# segment_driver_large.net
KiCad netlist of a schematic drawn in Altium Designer
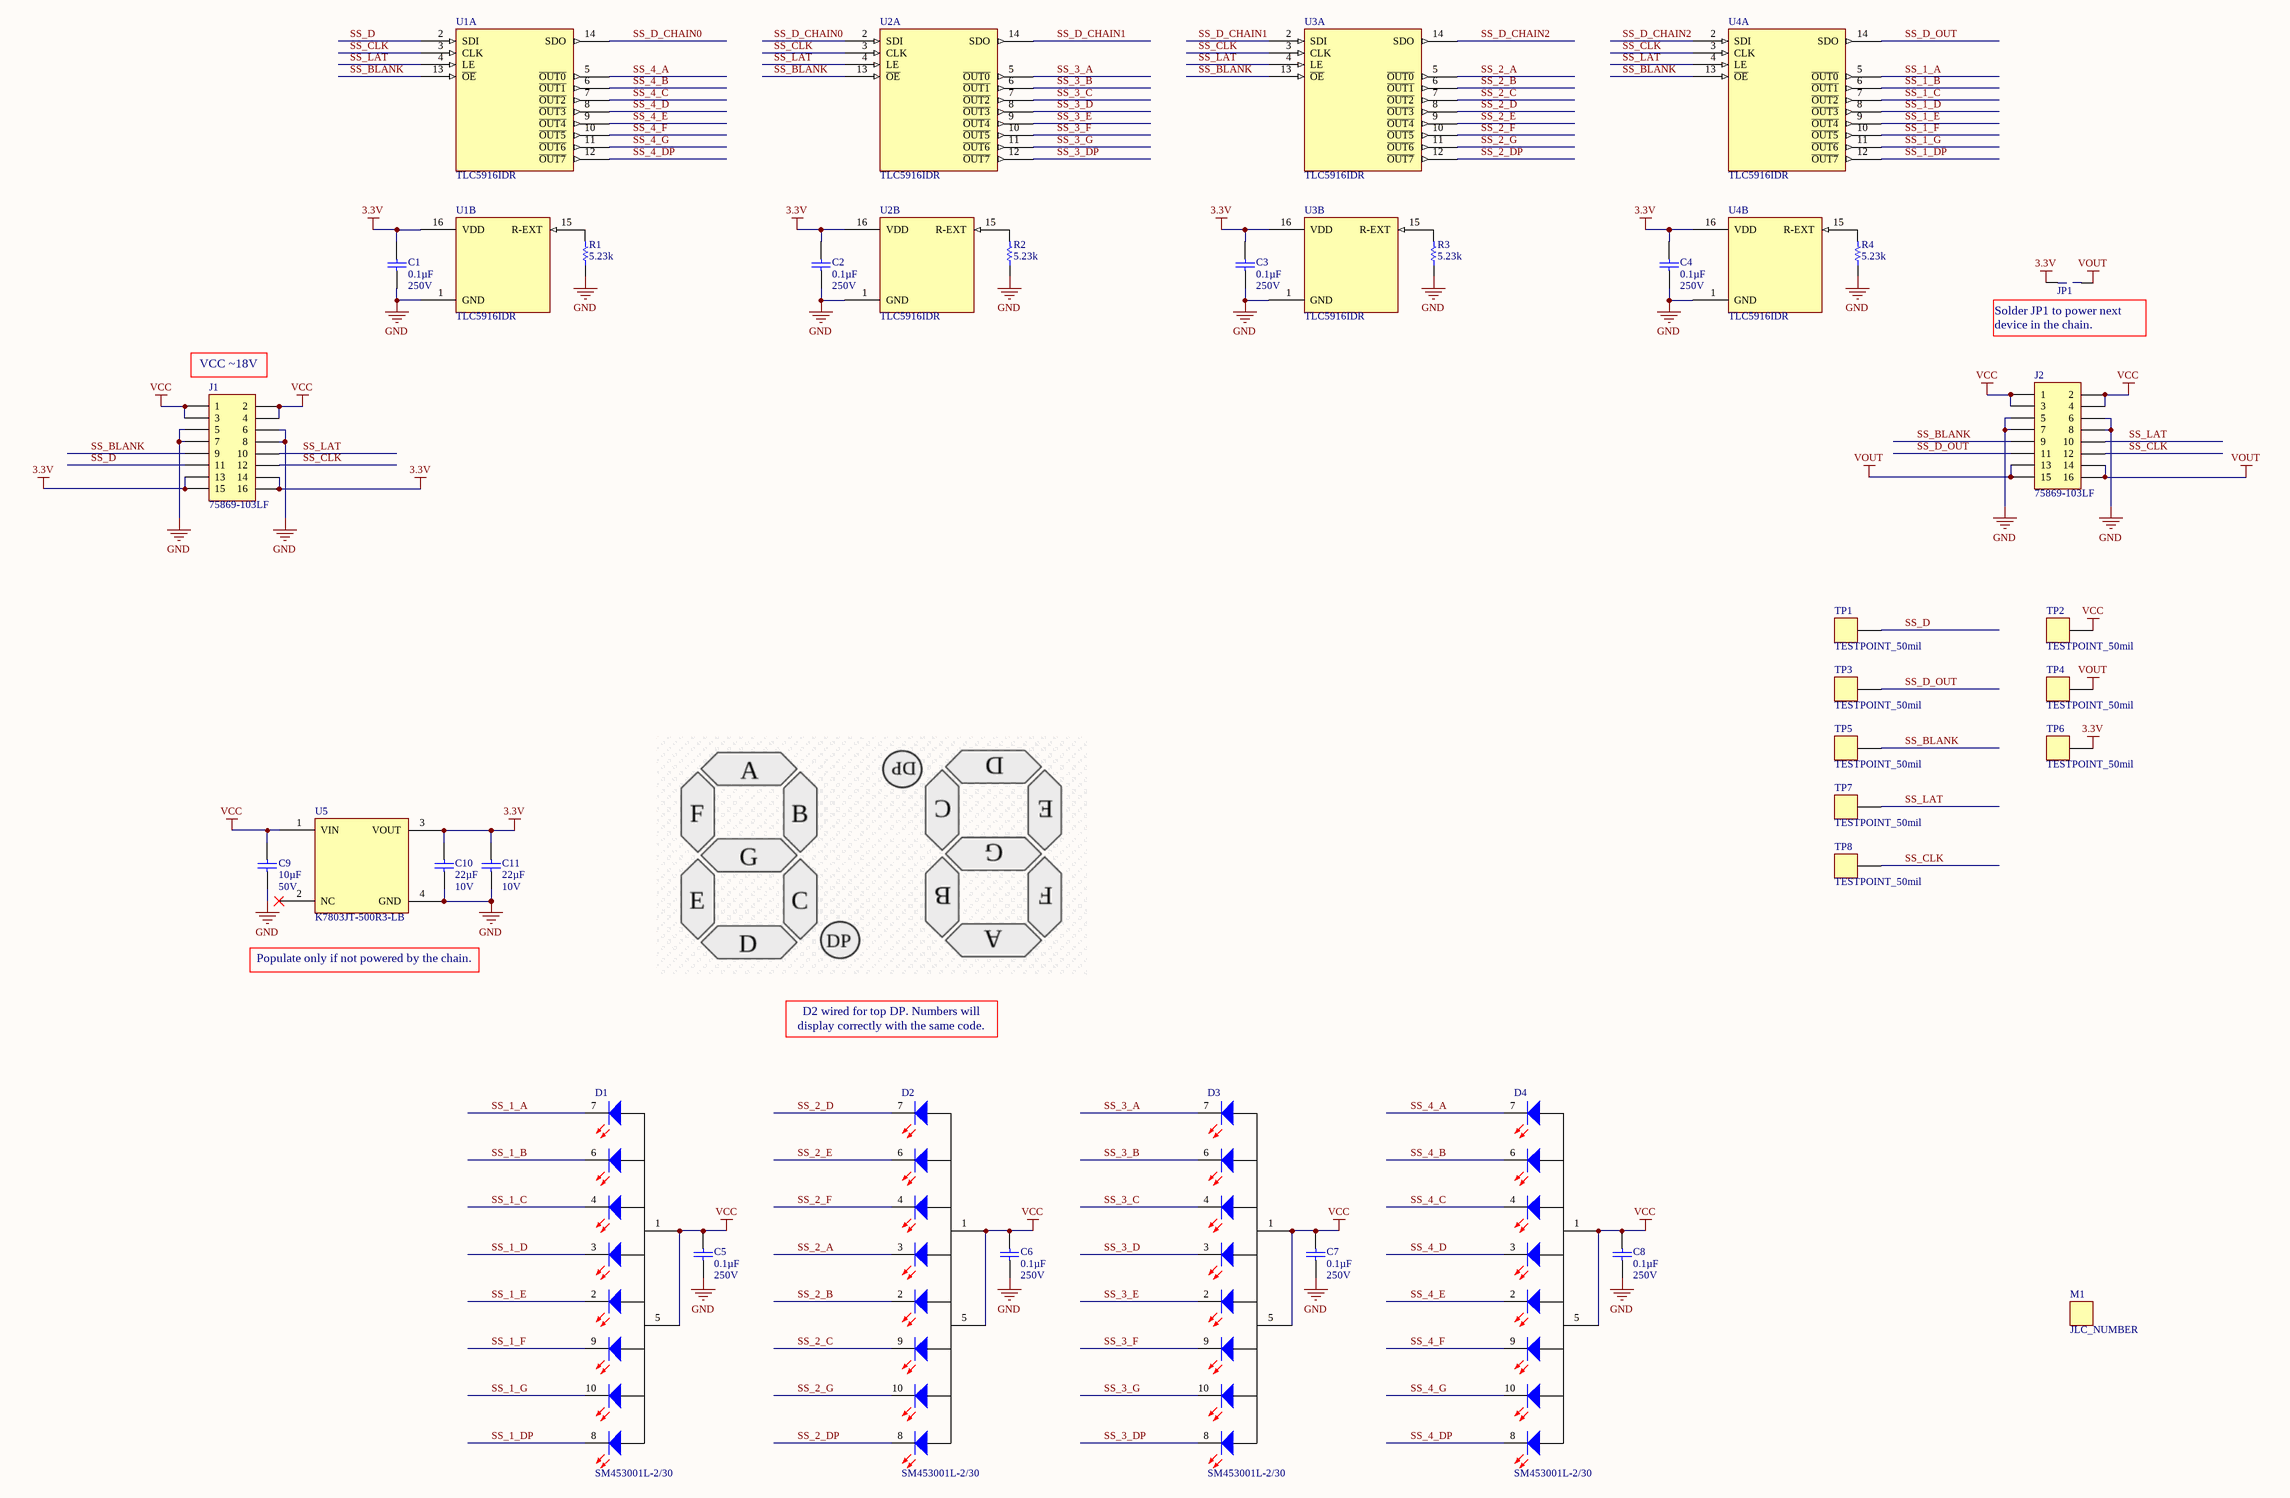
[diagram p0: segment_driver_large.SchDoc]

(export (version "E")
  (design (tool "Eeschema 10.0.6"))
  (components
    (comp (ref "C1")
      (value "0.1µF")
      (footprint "Chip0805")
      (description "CAP CER 0.1UF 250V 10% X7T 0805")
      (fields
        (field (name "VOLTAGE") "250V")
        (field (name "PARTNUMBER") "C2012X7T2E104K125AA")
        (field (name "MANUFACTURER") "TDK Corporation")
      )
      (libsource (lib "Passives") (part "CAP"))
    )
    (comp (ref "C2")
      (value "0.1µF")
      (footprint "Chip0805")
      (description "CAP CER 0.1UF 250V 10% X7T 0805")
      (fields
        (field (name "VOLTAGE") "250V")
        (field (name "PARTNUMBER") "C2012X7T2E104K125AA")
        (field (name "MANUFACTURER") "TDK Corporation")
      )
      (libsource (lib "Passives") (part "CAP"))
    )
    (comp (ref "C3")
      (value "0.1µF")
      (footprint "Chip0805")
      (description "CAP CER 0.1UF 250V 10% X7T 0805")
      (fields
        (field (name "VOLTAGE") "250V")
        (field (name "PARTNUMBER") "C2012X7T2E104K125AA")
        (field (name "MANUFACTURER") "TDK Corporation")
      )
      (libsource (lib "Passives") (part "CAP"))
    )
    (comp (ref "C4")
      (value "0.1µF")
      (footprint "Chip0805")
      (description "CAP CER 0.1UF 250V 10% X7T 0805")
      (fields
        (field (name "VOLTAGE") "250V")
        (field (name "PARTNUMBER") "C2012X7T2E104K125AA")
        (field (name "MANUFACTURER") "TDK Corporation")
      )
      (libsource (lib "Passives") (part "CAP"))
    )
    (comp (ref "C5")
      (value "0.1µF")
      (footprint "Chip0805")
      (description "CAP CER 0.1UF 250V 10% X7T 0805")
      (fields
        (field (name "VOLTAGE") "250V")
        (field (name "PARTNUMBER") "C2012X7T2E104K125AA")
        (field (name "MANUFACTURER") "TDK Corporation")
      )
      (libsource (lib "Passives") (part "CAP"))
    )
    (comp (ref "C6")
      (value "0.1µF")
      (footprint "Chip0805")
      (description "CAP CER 0.1UF 250V 10% X7T 0805")
      (fields
        (field (name "VOLTAGE") "250V")
        (field (name "PARTNUMBER") "C2012X7T2E104K125AA")
        (field (name "MANUFACTURER") "TDK Corporation")
      )
      (libsource (lib "Passives") (part "CAP"))
    )
    (comp (ref "C7")
      (value "0.1µF")
      (footprint "Chip0805")
      (description "CAP CER 0.1UF 250V 10% X7T 0805")
      (fields
        (field (name "VOLTAGE") "250V")
        (field (name "PARTNUMBER") "C2012X7T2E104K125AA")
        (field (name "MANUFACTURER") "TDK Corporation")
      )
      (libsource (lib "Passives") (part "CAP"))
    )
    (comp (ref "C8")
      (value "0.1µF")
      (footprint "Chip0805")
      (description "CAP CER 0.1UF 250V 10% X7T 0805")
      (fields
        (field (name "VOLTAGE") "250V")
        (field (name "PARTNUMBER") "C2012X7T2E104K125AA")
        (field (name "MANUFACTURER") "TDK Corporation")
      )
      (libsource (lib "Passives") (part "CAP"))
    )
    (comp (ref "C9")
      (value "10µF")
      (footprint "Chip1206")
      (description "CAP CER 10UF 50V 10% X5R 1206")
      (fields
        (field (name "VOLTAGE") "50V")
        (field (name "PARTNUMBER") "C3216X5R1H106K160AB")
        (field (name "MANUFACTURER") "TDK Corporation")
      )
      (libsource (lib "Passives") (part "CAP"))
    )
    (comp (ref "C10")
      (value "22µF")
      (footprint "Chip0805")
      (description "CAP CER 22UF 10V 20% X5R 0805")
      (fields
        (field (name "VOLTAGE") "10V")
        (field (name "PARTNUMBER") "C2012X5R1A226M085AC")
        (field (name "MANUFACTURER") "TDK Corporation")
      )
      (libsource (lib "Passives") (part "CAP"))
    )
    (comp (ref "C11")
      (value "22µF")
      (footprint "Chip0805")
      (description "CAP CER 22UF 10V 20% X5R 0805")
      (fields
        (field (name "VOLTAGE") "10V")
        (field (name "PARTNUMBER") "C2012X5R1A226M085AC")
        (field (name "MANUFACTURER") "TDK Corporation")
      )
      (libsource (lib "Passives") (part "CAP"))
    )
    (comp (ref "D1")
      (value "SM453001L-2/30")
      (footprint "ARKLED_SM453001L")
      (description "SEGMENTS DISPLAY 3.0\" COMMON ANODE")
      (fields (field (name "MANUFACTURER") "ARKLED"))
      (libsource (lib "Optoelectronics") (part "SEVEN_SEGMENT_ANODE"))
    )
    (comp (ref "D2")
      (value "SM453001L-2/30")
      (footprint "ARKLED_SM453001L")
      (description "SEGMENTS DISPLAY 3.0\" COMMON ANODE")
      (fields (field (name "MANUFACTURER") "ARKLED"))
      (libsource (lib "Optoelectronics") (part "SEVEN_SEGMENT_ANODE"))
    )
    (comp (ref "D3")
      (value "SM453001L-2/30")
      (footprint "ARKLED_SM453001L")
      (description "SEGMENTS DISPLAY 3.0\" COMMON ANODE")
      (fields (field (name "MANUFACTURER") "ARKLED"))
      (libsource (lib "Optoelectronics") (part "SEVEN_SEGMENT_ANODE"))
    )
    (comp (ref "D4")
      (value "SM453001L-2/30")
      (footprint "ARKLED_SM453001L")
      (description "SEGMENTS DISPLAY 3.0\" COMMON ANODE")
      (fields (field (name "MANUFACTURER") "ARKLED"))
      (libsource (lib "Optoelectronics") (part "SEVEN_SEGMENT_ANODE"))
    )
    (comp (ref "J1")
      (value "75869-103LF")
      (footprint "IDC_100_2x8")
      (description "CONN HEADER 16POS DUAL VERT PCB")
      (fields (field (name "MANUFACTURER") "FCI"))
      (libsource (lib "Connectors") (part "HEADER_2x8_ALT"))
    )
    (comp (ref "J2")
      (value "75869-103LF")
      (footprint "IDC_100_2x8")
      (description "CONN HEADER 16POS DUAL VERT PCB")
      (fields (field (name "MANUFACTURER") "FCI"))
      (libsource (lib "Connectors") (part "HEADER_2x8_ALT"))
    )
    (comp (ref "JP1")
      (value "JUMMPER_NO_CIRCLE")
      (footprint "JUMMPER_NO_CIRCLE")
      (libsource (lib "Mechanical") (part "JUMPER_NO"))
    )
    (comp (ref "M1")
      (value "JLC_NUMBER")
      (footprint "JLC_NUMBER")
      (description "JLC Order Number Location")
      (libsource (lib "Mechanical") (part "MECH_NO_BOM"))
    )
    (comp (ref "R1")
      (value "5.23k")
      (footprint "Chip0805")
      (description "RES 5.23K OHM 1/8W 1% 0805 SMD")
      (fields (field (name "PARTNUMBER") "CRCW08055K23FKEA") (field (name "MANUFACTURER") "Vishay Dale"))
      (libsource (lib "Passives") (part "RES"))
    )
    (comp (ref "R2")
      (value "5.23k")
      (footprint "Chip0805")
      (description "RES 5.23K OHM 1/8W 1% 0805 SMD")
      (fields (field (name "PARTNUMBER") "CRCW08055K23FKEA") (field (name "MANUFACTURER") "Vishay Dale"))
      (libsource (lib "Passives") (part "RES"))
    )
    (comp (ref "R3")
      (value "5.23k")
      (footprint "Chip0805")
      (description "RES 5.23K OHM 1/8W 1% 0805 SMD")
      (fields (field (name "PARTNUMBER") "CRCW08055K23FKEA") (field (name "MANUFACTURER") "Vishay Dale"))
      (libsource (lib "Passives") (part "RES"))
    )
    (comp (ref "R4")
      (value "5.23k")
      (footprint "Chip0805")
      (description "RES 5.23K OHM 1/8W 1% 0805 SMD")
      (fields (field (name "PARTNUMBER") "CRCW08055K23FKEA") (field (name "MANUFACTURER") "Vishay Dale"))
      (libsource (lib "Passives") (part "RES"))
    )
    (comp (ref "TP1")
      (value "TESTPOINT_50mil")
      (footprint "TESTPOINT_50mil")
      (libsource (lib "Mechanical") (part "TESTPOINT_NO_BOM"))
    )
    (comp (ref "TP2")
      (value "TESTPOINT_50mil")
      (footprint "TESTPOINT_50mil")
      (libsource (lib "Mechanical") (part "TESTPOINT_NO_BOM"))
    )
    (comp (ref "TP3")
      (value "TESTPOINT_50mil")
      (footprint "TESTPOINT_50mil")
      (libsource (lib "Mechanical") (part "TESTPOINT_NO_BOM"))
    )
    (comp (ref "TP4")
      (value "TESTPOINT_50mil")
      (footprint "TESTPOINT_50mil")
      (libsource (lib "Mechanical") (part "TESTPOINT_NO_BOM"))
    )
    (comp (ref "TP5")
      (value "TESTPOINT_50mil")
      (footprint "TESTPOINT_50mil")
      (libsource (lib "Mechanical") (part "TESTPOINT_NO_BOM"))
    )
    (comp (ref "TP6")
      (value "TESTPOINT_50mil")
      (footprint "TESTPOINT_50mil")
      (libsource (lib "Mechanical") (part "TESTPOINT_NO_BOM"))
    )
    (comp (ref "TP7")
      (value "TESTPOINT_50mil")
      (footprint "TESTPOINT_50mil")
      (libsource (lib "Mechanical") (part "TESTPOINT_NO_BOM"))
    )
    (comp (ref "TP8")
      (value "TESTPOINT_50mil")
      (footprint "TESTPOINT_50mil")
      (libsource (lib "Mechanical") (part "TESTPOINT_NO_BOM"))
    )
    (comp (ref "U1")
      (value "TLC5916IDR")
      (footprint "16-SOIC")
      (description "IC LED DRVR LINEAR 120MA 16SOIC")
      (fields (field (name "MANUFACTURER") "Texas Instruments"))
      (libsource (lib "ICs") (part "TI_TLC591x"))
    )
    (comp (ref "U2")
      (value "TLC5916IDR")
      (footprint "16-SOIC")
      (description "IC LED DRVR LINEAR 120MA 16SOIC")
      (fields (field (name "MANUFACTURER") "Texas Instruments"))
      (libsource (lib "ICs") (part "TI_TLC591x"))
    )
    (comp (ref "U3")
      (value "TLC5916IDR")
      (footprint "16-SOIC")
      (description "IC LED DRVR LINEAR 120MA 16SOIC")
      (fields (field (name "MANUFACTURER") "Texas Instruments"))
      (libsource (lib "ICs") (part "TI_TLC591x"))
    )
    (comp (ref "U4")
      (value "TLC5916IDR")
      (footprint "16-SOIC")
      (description "IC LED DRVR LINEAR 120MA 16SOIC")
      (fields (field (name "MANUFACTURER") "Texas Instruments"))
      (libsource (lib "ICs") (part "TI_TLC591x"))
    )
    (comp (ref "U5")
      (value "K7803JT-500R3-LB")
      (footprint "MORNSUN_K78XXJT-500R3-LB")
      (description "LINEAR REGULATOR REPLACEMENT DC")
      (fields (field (name "MANUFACTURER") "Mornsun America, LLC"))
      (libsource (lib "ICs") (part "MORNSUN_K78XXJT-500R3-LB"))
    )
  )
  (nets
    (net (code "1") (name "/SS_1_A") (class "Default")
      (node (ref "D1") (pin "7") (pinfunction "A_7") (pintype "passive"))
      (node (ref "U4") (pin "5") (pinfunction "~{OUT0}_5") (pintype "output"))
    )
    (net (code "2") (name "/SS_1_B") (class "Default")
      (node (ref "D1") (pin "6") (pinfunction "B_6") (pintype "passive"))
      (node (ref "U4") (pin "6") (pinfunction "~{OUT1}_6") (pintype "output"))
    )
    (net (code "3") (name "/SS_1_C") (class "Default")
      (node (ref "D1") (pin "4") (pinfunction "C_4") (pintype "passive"))
      (node (ref "U4") (pin "7") (pinfunction "~{OUT2}_7") (pintype "output"))
    )
    (net (code "4") (name "/SS_1_D") (class "Default")
      (node (ref "D1") (pin "3") (pinfunction "D_3") (pintype "passive"))
      (node (ref "U4") (pin "8") (pinfunction "~{OUT3}_8") (pintype "output"))
    )
    (net (code "5") (name "/SS_1_DP") (class "Default")
      (node (ref "D1") (pin "8") (pinfunction "DP_8") (pintype "passive"))
      (node (ref "U4") (pin "12") (pinfunction "~{OUT7}_12") (pintype "output"))
    )
    (net (code "6") (name "/SS_1_E") (class "Default")
      (node (ref "D1") (pin "2") (pinfunction "E_2") (pintype "passive"))
      (node (ref "U4") (pin "9") (pinfunction "~{OUT4}_9") (pintype "output"))
    )
    (net (code "7") (name "/SS_1_F") (class "Default")
      (node (ref "D1") (pin "9") (pinfunction "F_9") (pintype "passive"))
      (node (ref "U4") (pin "10") (pinfunction "~{OUT5}_10") (pintype "output"))
    )
    (net (code "8") (name "/SS_1_G") (class "Default")
      (node (ref "D1") (pin "10") (pinfunction "G_10") (pintype "passive"))
      (node (ref "U4") (pin "11") (pinfunction "~{OUT6}_11") (pintype "output"))
    )
    (net (code "9") (name "/SS_2_A") (class "Default")
      (node (ref "D2") (pin "3") (pinfunction "D_3") (pintype "passive"))
      (node (ref "U3") (pin "5") (pinfunction "~{OUT0}_5") (pintype "output"))
    )
    (net (code "10") (name "/SS_2_B") (class "Default")
      (node (ref "D2") (pin "2") (pinfunction "E_2") (pintype "passive"))
      (node (ref "U3") (pin "6") (pinfunction "~{OUT1}_6") (pintype "output"))
    )
    (net (code "11") (name "/SS_2_C") (class "Default")
      (node (ref "D2") (pin "9") (pinfunction "F_9") (pintype "passive"))
      (node (ref "U3") (pin "7") (pinfunction "~{OUT2}_7") (pintype "output"))
    )
    (net (code "12") (name "/SS_2_D") (class "Default")
      (node (ref "D2") (pin "7") (pinfunction "A_7") (pintype "passive"))
      (node (ref "U3") (pin "8") (pinfunction "~{OUT3}_8") (pintype "output"))
    )
    (net (code "13") (name "/SS_2_DP") (class "Default")
      (node (ref "D2") (pin "8") (pinfunction "DP_8") (pintype "passive"))
      (node (ref "U3") (pin "12") (pinfunction "~{OUT7}_12") (pintype "output"))
    )
    (net (code "14") (name "/SS_2_E") (class "Default")
      (node (ref "D2") (pin "6") (pinfunction "B_6") (pintype "passive"))
      (node (ref "U3") (pin "9") (pinfunction "~{OUT4}_9") (pintype "output"))
    )
    (net (code "15") (name "/SS_2_F") (class "Default")
      (node (ref "D2") (pin "4") (pinfunction "C_4") (pintype "passive"))
      (node (ref "U3") (pin "10") (pinfunction "~{OUT5}_10") (pintype "output"))
    )
    (net (code "16") (name "/SS_2_G") (class "Default")
      (node (ref "D2") (pin "10") (pinfunction "G_10") (pintype "passive"))
      (node (ref "U3") (pin "11") (pinfunction "~{OUT6}_11") (pintype "output"))
    )
    (net (code "17") (name "/SS_3_A") (class "Default")
      (node (ref "D3") (pin "7") (pinfunction "A_7") (pintype "passive"))
      (node (ref "U2") (pin "5") (pinfunction "~{OUT0}_5") (pintype "output"))
    )
    (net (code "18") (name "/SS_3_B") (class "Default")
      (node (ref "D3") (pin "6") (pinfunction "B_6") (pintype "passive"))
      (node (ref "U2") (pin "6") (pinfunction "~{OUT1}_6") (pintype "output"))
    )
    (net (code "19") (name "/SS_3_C") (class "Default")
      (node (ref "D3") (pin "4") (pinfunction "C_4") (pintype "passive"))
      (node (ref "U2") (pin "7") (pinfunction "~{OUT2}_7") (pintype "output"))
    )
    (net (code "20") (name "/SS_3_D") (class "Default")
      (node (ref "D3") (pin "3") (pinfunction "D_3") (pintype "passive"))
      (node (ref "U2") (pin "8") (pinfunction "~{OUT3}_8") (pintype "output"))
    )
    (net (code "21") (name "/SS_3_DP") (class "Default")
      (node (ref "D3") (pin "8") (pinfunction "DP_8") (pintype "passive"))
      (node (ref "U2") (pin "12") (pinfunction "~{OUT7}_12") (pintype "output"))
    )
    (net (code "22") (name "/SS_3_E") (class "Default")
      (node (ref "D3") (pin "2") (pinfunction "E_2") (pintype "passive"))
      (node (ref "U2") (pin "9") (pinfunction "~{OUT4}_9") (pintype "output"))
    )
    (net (code "23") (name "/SS_3_F") (class "Default")
      (node (ref "D3") (pin "9") (pinfunction "F_9") (pintype "passive"))
      (node (ref "U2") (pin "10") (pinfunction "~{OUT5}_10") (pintype "output"))
    )
    (net (code "24") (name "/SS_3_G") (class "Default")
      (node (ref "D3") (pin "10") (pinfunction "G_10") (pintype "passive"))
      (node (ref "U2") (pin "11") (pinfunction "~{OUT6}_11") (pintype "output"))
    )
    (net (code "25") (name "/SS_4_A") (class "Default")
      (node (ref "D4") (pin "7") (pinfunction "A_7") (pintype "passive"))
      (node (ref "U1") (pin "5") (pinfunction "~{OUT0}_5") (pintype "output"))
    )
    (net (code "26") (name "/SS_4_B") (class "Default")
      (node (ref "D4") (pin "6") (pinfunction "B_6") (pintype "passive"))
      (node (ref "U1") (pin "6") (pinfunction "~{OUT1}_6") (pintype "output"))
    )
    (net (code "27") (name "/SS_4_C") (class "Default")
      (node (ref "D4") (pin "4") (pinfunction "C_4") (pintype "passive"))
      (node (ref "U1") (pin "7") (pinfunction "~{OUT2}_7") (pintype "output"))
    )
    (net (code "28") (name "/SS_4_D") (class "Default")
      (node (ref "D4") (pin "3") (pinfunction "D_3") (pintype "passive"))
      (node (ref "U1") (pin "8") (pinfunction "~{OUT3}_8") (pintype "output"))
    )
    (net (code "29") (name "/SS_4_DP") (class "Default")
      (node (ref "D4") (pin "8") (pinfunction "DP_8") (pintype "passive"))
      (node (ref "U1") (pin "12") (pinfunction "~{OUT7}_12") (pintype "output"))
    )
    (net (code "30") (name "/SS_4_E") (class "Default")
      (node (ref "D4") (pin "2") (pinfunction "E_2") (pintype "passive"))
      (node (ref "U1") (pin "9") (pinfunction "~{OUT4}_9") (pintype "output"))
    )
    (net (code "31") (name "/SS_4_F") (class "Default")
      (node (ref "D4") (pin "9") (pinfunction "F_9") (pintype "passive"))
      (node (ref "U1") (pin "10") (pinfunction "~{OUT5}_10") (pintype "output"))
    )
    (net (code "32") (name "/SS_4_G") (class "Default")
      (node (ref "D4") (pin "10") (pinfunction "G_10") (pintype "passive"))
      (node (ref "U1") (pin "11") (pinfunction "~{OUT6}_11") (pintype "output"))
    )
    (net (code "33") (name "/SS_BLANK") (class "Default")
      (node (ref "J1") (pin "9") (pinfunction "9_9") (pintype "passive"))
      (node (ref "J2") (pin "9") (pinfunction "9_9") (pintype "passive"))
      (node (ref "TP5") (pin "1") (pinfunction "1_1") (pintype "passive"))
      (node (ref "U1") (pin "13") (pinfunction "~{OE}_13") (pintype "input"))
      (node (ref "U2") (pin "13") (pinfunction "~{OE}_13") (pintype "input"))
      (node (ref "U3") (pin "13") (pinfunction "~{OE}_13") (pintype "input"))
      (node (ref "U4") (pin "13") (pinfunction "~{OE}_13") (pintype "input"))
    )
    (net (code "34") (name "/SS_CLK") (class "Default")
      (node (ref "J1") (pin "12") (pinfunction "12_12") (pintype "passive"))
      (node (ref "J2") (pin "12") (pinfunction "12_12") (pintype "passive"))
      (node (ref "TP8") (pin "1") (pinfunction "1_1") (pintype "passive"))
      (node (ref "U1") (pin "3") (pinfunction "CLK_3") (pintype "input"))
      (node (ref "U2") (pin "3") (pinfunction "CLK_3") (pintype "input"))
      (node (ref "U3") (pin "3") (pinfunction "CLK_3") (pintype "input"))
      (node (ref "U4") (pin "3") (pinfunction "CLK_3") (pintype "input"))
    )
    (net (code "35") (name "/SS_D") (class "Default")
      (node (ref "J1") (pin "11") (pinfunction "11_11") (pintype "passive"))
      (node (ref "TP1") (pin "1") (pinfunction "1_1") (pintype "passive"))
      (node (ref "U1") (pin "2") (pinfunction "SDI_2") (pintype "input"))
    )
    (net (code "36") (name "/SS_D_CHAIN0") (class "Default")
      (node (ref "U1") (pin "14") (pinfunction "SDO_14") (pintype "output"))
      (node (ref "U2") (pin "2") (pinfunction "SDI_2") (pintype "input"))
    )
    (net (code "37") (name "/SS_D_CHAIN1") (class "Default")
      (node (ref "U2") (pin "14") (pinfunction "SDO_14") (pintype "output"))
      (node (ref "U3") (pin "2") (pinfunction "SDI_2") (pintype "input"))
    )
    (net (code "38") (name "/SS_D_CHAIN2") (class "Default")
      (node (ref "U3") (pin "14") (pinfunction "SDO_14") (pintype "output"))
      (node (ref "U4") (pin "2") (pinfunction "SDI_2") (pintype "input"))
    )
    (net (code "39") (name "/SS_D_OUT") (class "Default")
      (node (ref "J2") (pin "11") (pinfunction "11_11") (pintype "passive"))
      (node (ref "TP3") (pin "1") (pinfunction "1_1") (pintype "passive"))
      (node (ref "U4") (pin "14") (pinfunction "SDO_14") (pintype "output"))
    )
    (net (code "40") (name "/SS_LAT") (class "Default")
      (node (ref "J1") (pin "10") (pinfunction "10_10") (pintype "passive"))
      (node (ref "J2") (pin "10") (pinfunction "10_10") (pintype "passive"))
      (node (ref "TP7") (pin "1") (pinfunction "1_1") (pintype "passive"))
      (node (ref "U1") (pin "4") (pinfunction "LE_4") (pintype "input"))
      (node (ref "U2") (pin "4") (pinfunction "LE_4") (pintype "input"))
      (node (ref "U3") (pin "4") (pinfunction "LE_4") (pintype "input"))
      (node (ref "U4") (pin "4") (pinfunction "LE_4") (pintype "input"))
    )
    (net (code "41") (name "3.3V") (class "Default")
      (node (ref "C1") (pin "2") (pinfunction "2_2") (pintype "passive"))
      (node (ref "C10") (pin "2") (pinfunction "2_2") (pintype "passive"))
      (node (ref "C11") (pin "2") (pinfunction "2_2") (pintype "passive"))
      (node (ref "C2") (pin "2") (pinfunction "2_2") (pintype "passive"))
      (node (ref "C3") (pin "2") (pinfunction "2_2") (pintype "passive"))
      (node (ref "C4") (pin "2") (pinfunction "2_2") (pintype "passive"))
      (node (ref "J1") (pin "13") (pinfunction "13_13") (pintype "passive"))
      (node (ref "J1") (pin "14") (pinfunction "14_14") (pintype "passive"))
      (node (ref "J1") (pin "15") (pinfunction "15_15") (pintype "passive"))
      (node (ref "J1") (pin "16") (pinfunction "16_16") (pintype "passive"))
      (node (ref "JP1") (pin "2") (pinfunction "2_2") (pintype "passive"))
      (node (ref "TP6") (pin "1") (pinfunction "1_1") (pintype "passive"))
      (node (ref "U1") (pin "16") (pinfunction "VDD_16") (pintype "passive"))
      (node (ref "U2") (pin "16") (pinfunction "VDD_16") (pintype "passive"))
      (node (ref "U3") (pin "16") (pinfunction "VDD_16") (pintype "passive"))
      (node (ref "U4") (pin "16") (pinfunction "VDD_16") (pintype "passive"))
      (node (ref "U5") (pin "3") (pinfunction "VOUT_3") (pintype "passive"))
    )
    (net (code "42") (name "GND") (class "Default")
      (node (ref "C1") (pin "1") (pinfunction "1_1") (pintype "passive"))
      (node (ref "C10") (pin "1") (pinfunction "1_1") (pintype "passive"))
      (node (ref "C11") (pin "1") (pinfunction "1_1") (pintype "passive"))
      (node (ref "C2") (pin "1") (pinfunction "1_1") (pintype "passive"))
      (node (ref "C3") (pin "1") (pinfunction "1_1") (pintype "passive"))
      (node (ref "C4") (pin "1") (pinfunction "1_1") (pintype "passive"))
      (node (ref "C5") (pin "1") (pinfunction "1_1") (pintype "passive"))
      (node (ref "C6") (pin "1") (pinfunction "1_1") (pintype "passive"))
      (node (ref "C7") (pin "1") (pinfunction "1_1") (pintype "passive"))
      (node (ref "C8") (pin "1") (pinfunction "1_1") (pintype "passive"))
      (node (ref "C9") (pin "1") (pinfunction "1_1") (pintype "passive"))
      (node (ref "J1") (pin "5") (pinfunction "5_5") (pintype "passive"))
      (node (ref "J1") (pin "6") (pinfunction "6_6") (pintype "passive"))
      (node (ref "J1") (pin "7") (pinfunction "7_7") (pintype "passive"))
      (node (ref "J1") (pin "8") (pinfunction "8_8") (pintype "passive"))
      (node (ref "J2") (pin "5") (pinfunction "5_5") (pintype "passive"))
      (node (ref "J2") (pin "6") (pinfunction "6_6") (pintype "passive"))
      (node (ref "J2") (pin "7") (pinfunction "7_7") (pintype "passive"))
      (node (ref "J2") (pin "8") (pinfunction "8_8") (pintype "passive"))
      (node (ref "R1") (pin "1") (pinfunction "1_1") (pintype "passive"))
      (node (ref "R2") (pin "1") (pinfunction "1_1") (pintype "passive"))
      (node (ref "R3") (pin "1") (pinfunction "1_1") (pintype "passive"))
      (node (ref "R4") (pin "1") (pinfunction "1_1") (pintype "passive"))
      (node (ref "U1") (pin "1") (pinfunction "GND_1") (pintype "passive"))
      (node (ref "U2") (pin "1") (pinfunction "GND_1") (pintype "passive"))
      (node (ref "U3") (pin "1") (pinfunction "GND_1") (pintype "passive"))
      (node (ref "U4") (pin "1") (pinfunction "GND_1") (pintype "passive"))
      (node (ref "U5") (pin "4") (pinfunction "GND_4") (pintype "passive"))
    )
    (net (code "43") (name "Net-(U1B-R-EXT)") (class "Default")
      (node (ref "R1") (pin "2") (pinfunction "2_2") (pintype "passive"))
      (node (ref "U1") (pin "15") (pinfunction "R-EXT_15") (pintype "input"))
    )
    (net (code "44") (name "Net-(U2B-R-EXT)") (class "Default")
      (node (ref "R2") (pin "2") (pinfunction "2_2") (pintype "passive"))
      (node (ref "U2") (pin "15") (pinfunction "R-EXT_15") (pintype "input"))
    )
    (net (code "45") (name "Net-(U3B-R-EXT)") (class "Default")
      (node (ref "R3") (pin "2") (pinfunction "2_2") (pintype "passive"))
      (node (ref "U3") (pin "15") (pinfunction "R-EXT_15") (pintype "input"))
    )
    (net (code "46") (name "Net-(U4B-R-EXT)") (class "Default")
      (node (ref "R4") (pin "2") (pinfunction "2_2") (pintype "passive"))
      (node (ref "U4") (pin "15") (pinfunction "R-EXT_15") (pintype "input"))
    )
    (net (code "47") (name "VCC") (class "Default")
      (node (ref "C5") (pin "2") (pinfunction "2_2") (pintype "passive"))
      (node (ref "C6") (pin "2") (pinfunction "2_2") (pintype "passive"))
      (node (ref "C7") (pin "2") (pinfunction "2_2") (pintype "passive"))
      (node (ref "C8") (pin "2") (pinfunction "2_2") (pintype "passive"))
      (node (ref "C9") (pin "2") (pinfunction "2_2") (pintype "passive"))
      (node (ref "D1") (pin "1") (pinfunction "A_1") (pintype "passive"))
      (node (ref "D1") (pin "5") (pinfunction "A_5") (pintype "passive"))
      (node (ref "D2") (pin "1") (pinfunction "A_1") (pintype "passive"))
      (node (ref "D2") (pin "5") (pinfunction "A_5") (pintype "passive"))
      (node (ref "D3") (pin "1") (pinfunction "A_1") (pintype "passive"))
      (node (ref "D3") (pin "5") (pinfunction "A_5") (pintype "passive"))
      (node (ref "D4") (pin "1") (pinfunction "A_1") (pintype "passive"))
      (node (ref "D4") (pin "5") (pinfunction "A_5") (pintype "passive"))
      (node (ref "J1") (pin "1") (pinfunction "1_1") (pintype "passive"))
      (node (ref "J1") (pin "2") (pinfunction "2_2") (pintype "passive"))
      (node (ref "J1") (pin "3") (pinfunction "3_3") (pintype "passive"))
      (node (ref "J1") (pin "4") (pinfunction "4_4") (pintype "passive"))
      (node (ref "J2") (pin "1") (pinfunction "1_1") (pintype "passive"))
      (node (ref "J2") (pin "2") (pinfunction "2_2") (pintype "passive"))
      (node (ref "J2") (pin "3") (pinfunction "3_3") (pintype "passive"))
      (node (ref "J2") (pin "4") (pinfunction "4_4") (pintype "passive"))
      (node (ref "TP2") (pin "1") (pinfunction "1_1") (pintype "passive"))
      (node (ref "U5") (pin "1") (pinfunction "VIN_1") (pintype "passive"))
    )
    (net (code "48") (name "VOUT") (class "Default")
      (node (ref "J2") (pin "13") (pinfunction "13_13") (pintype "passive"))
      (node (ref "J2") (pin "14") (pinfunction "14_14") (pintype "passive"))
      (node (ref "J2") (pin "15") (pinfunction "15_15") (pintype "passive"))
      (node (ref "J2") (pin "16") (pinfunction "16_16") (pintype "passive"))
      (node (ref "JP1") (pin "1") (pinfunction "1_1") (pintype "passive"))
      (node (ref "TP4") (pin "1") (pinfunction "1_1") (pintype "passive"))
    )
    (net (code "49") (name "unconnected-(U5-NC-Pad2)") (class "Default")
      (node (ref "U5") (pin "2") (pinfunction "NC_2") (pintype "passive+no_connect"))
    )
  )
)
